# nixie_clock_schematics.net
KiCad netlist of a schematic drawn in EAGLE
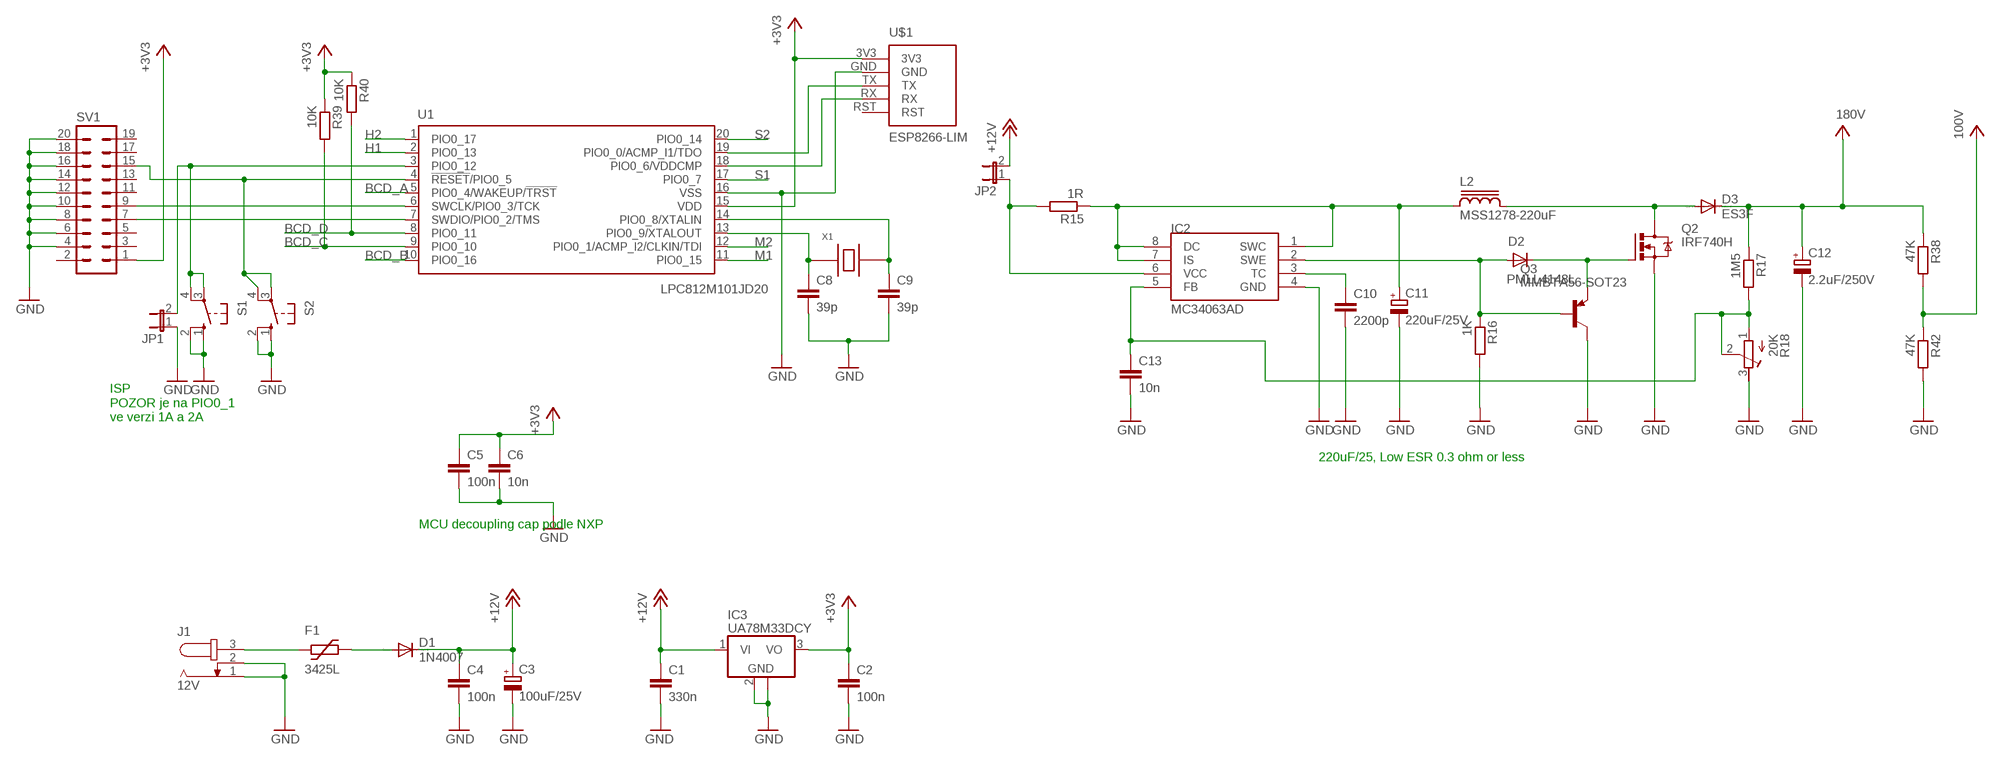
[diagram p0: schematic, sheet 1]
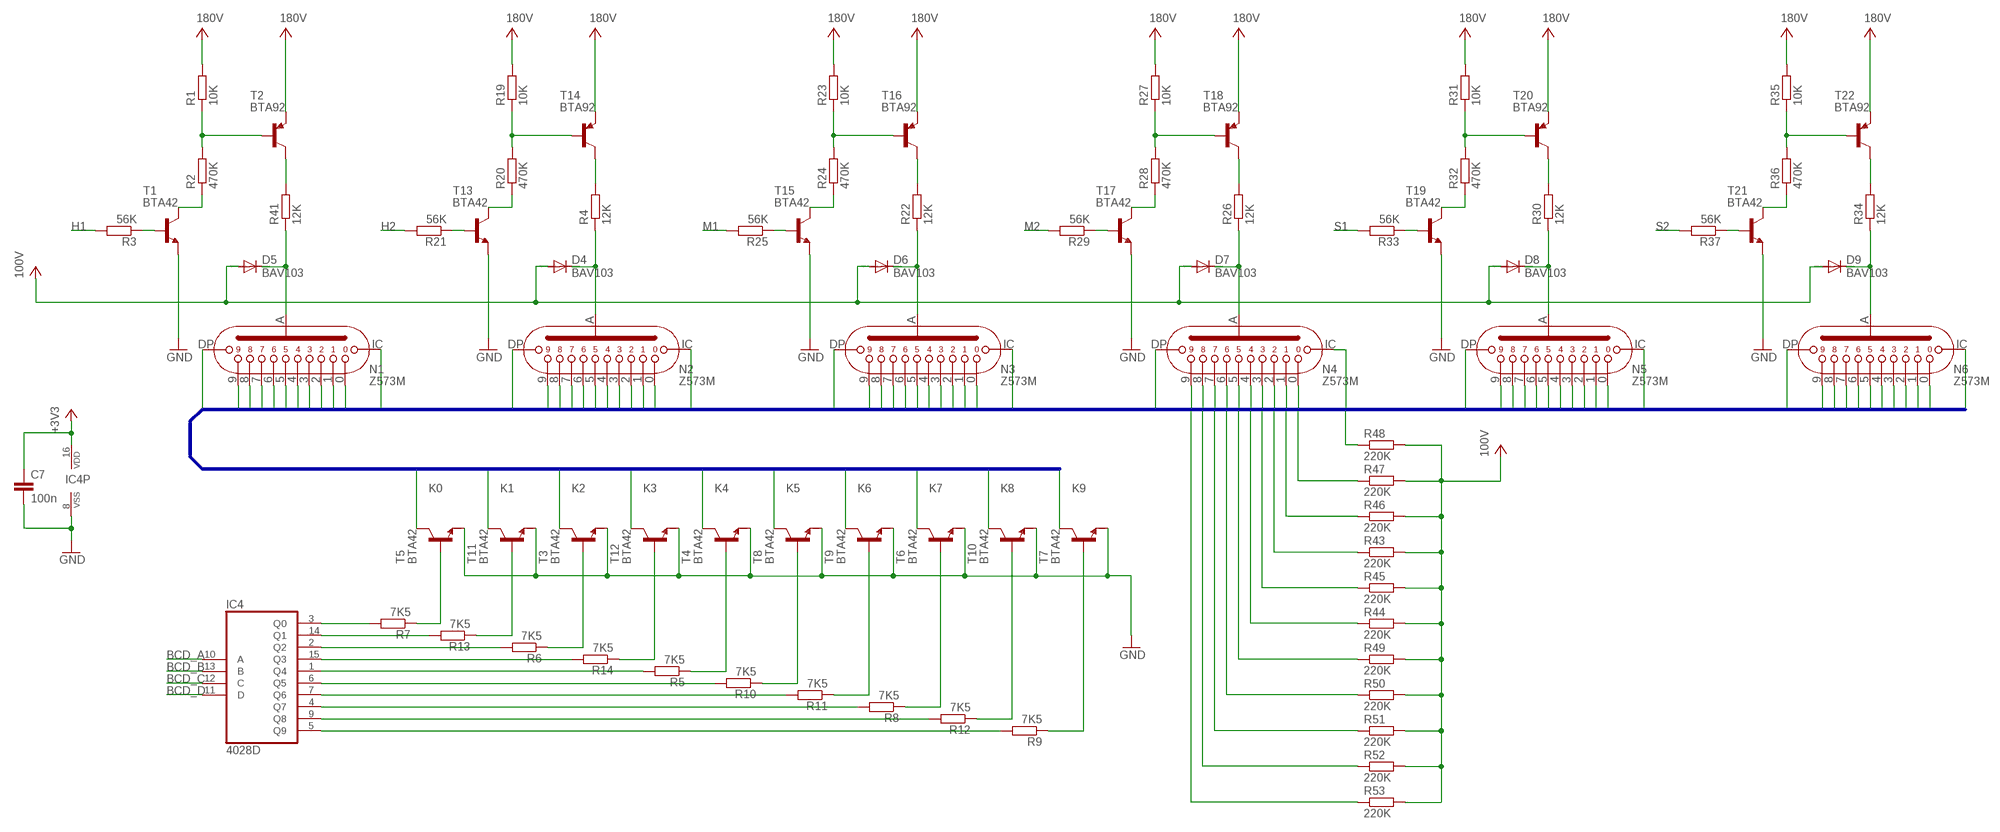
[diagram p1: schematic, sheet 2]

(export (version "E")
  (design (tool "Eeschema 10.0.6"))
  (components
    (comp (ref "C1")
      (value "330n")
      (footprint "eagle-import:C1206")
      (libsource (lib "eagle-import") (part "C-EUC1206"))
    )
    (comp (ref "C2")
      (value "100n")
      (footprint "eagle-import:C1206")
      (libsource (lib "eagle-import") (part "C-EUC1206"))
    )
    (comp (ref "C3")
      (value "100uF/25V")
      (footprint "eagle-import:153CLV-0605")
      (libsource (lib "eagle-import") (part "CPOL-EU153CLV-0605"))
    )
    (comp (ref "C4")
      (value "100n")
      (footprint "eagle-import:C1206")
      (libsource (lib "eagle-import") (part "C-EUC1206"))
    )
    (comp (ref "C5")
      (value "100n")
      (footprint "eagle-import:C1206")
      (libsource (lib "eagle-import") (part "C-EUC1206"))
    )
    (comp (ref "C6")
      (value "10n")
      (footprint "eagle-import:C1206")
      (libsource (lib "eagle-import") (part "C-EUC1206"))
    )
    (comp (ref "C8")
      (value "39p")
      (footprint "eagle-import:C0805")
      (libsource (lib "eagle-import") (part "C-EUC0805"))
    )
    (comp (ref "C9")
      (value "39p")
      (footprint "eagle-import:C0805")
      (libsource (lib "eagle-import") (part "C-EUC0805"))
    )
    (comp (ref "C10")
      (value "2200p")
      (footprint "eagle-import:C1206")
      (libsource (lib "eagle-import") (part "C-EUC1206"))
    )
    (comp (ref "C11")
      (value "220uF/25V")
      (footprint "eagle-import:153CLV-0605")
      (libsource (lib "eagle-import") (part "CPOL-EU153CLV-0605"))
    )
    (comp (ref "C12")
      (value "2.2uF/250V")
      (footprint "eagle-import:E2,5-6")
      (libsource (lib "eagle-import") (part "CPOL-EUE2.5-6"))
    )
    (comp (ref "C13")
      (value "10n")
      (footprint "eagle-import:C1206")
      (libsource (lib "eagle-import") (part "C-EUC1206"))
    )
    (comp (ref "D1")
      (value "1N4007")
      (footprint "eagle-import:MELF-MLL41")
      (libsource (lib "eagle-import") (part "DIODE-MELF-MLL41"))
    )
    (comp (ref "D2")
      (value "PMLL4148L")
      (footprint "eagle-import:SOD80C")
      (libsource (lib "eagle-import") (part "PMLL4148L"))
    )
    (comp (ref "D3")
      (value "ES3F")
      (footprint "eagle-import:SMC")
      (libsource (lib "eagle-import") (part "DIODE-SMC"))
    )
    (comp (ref "F1")
      (value "3425L")
      (footprint "eagle-import:3425L")
      (libsource (lib "eagle-import") (part "3425L"))
    )
    (comp (ref "IC2")
      (value "MC34063AD")
      (footprint "eagle-import:SOIC8")
      (libsource (lib "eagle-import") (part "MC34063AD"))
    )
    (comp (ref "IC3")
      (value "UA78M33DCY")
      (footprint "eagle-import:SOT223")
      (libsource (lib "eagle-import") (part "UA78MDCY33"))
    )
    (comp (ref "J1")
      (value "12V")
      (footprint "eagle-import:SPC4077")
      (libsource (lib "eagle-import") (part "JACK-PLUG0"))
    )
    (comp (ref "JP1")
      (value "JP1E")
      (footprint "eagle-import:JP1")
      (libsource (lib "eagle-import") (part "JP1E"))
    )
    (comp (ref "JP2")
      (value "JP1E")
      (footprint "eagle-import:JP1")
      (libsource (lib "eagle-import") (part "JP1E"))
    )
    (comp (ref "L2")
      (value "MSS1278-220uF")
      (footprint "eagle-import:MSS1278")
      (libsource (lib "eagle-import") (part "MSS1278"))
    )
    (comp (ref "Q2")
      (value "IRF740H")
      (footprint "eagle-import:TO220BH")
      (libsource (lib "eagle-import") (part "IRF740H"))
    )
    (comp (ref "Q3")
      (value "MMBTA56-SOT23")
      (footprint "eagle-import:SOT23")
      (libsource (lib "eagle-import") (part "-?SOT23MMBTA56"))
    )
    (comp (ref "R15")
      (value "1R")
      (footprint "eagle-import:R1206")
      (libsource (lib "eagle-import") (part "R-EU_R1206"))
    )
    (comp (ref "R16")
      (value "1K")
      (footprint "eagle-import:R1206")
      (libsource (lib "eagle-import") (part "R-EU_R1206"))
    )
    (comp (ref "R17")
      (value "1M5")
      (footprint "eagle-import:R1206")
      (libsource (lib "eagle-import") (part "R-EU_R1206"))
    )
    (comp (ref "R18")
      (value "20K")
      (footprint "eagle-import:RTRIM4G_J")
      (libsource (lib "eagle-import") (part "R-TRIMM4G/J"))
    )
    (comp (ref "R38")
      (value "47K")
      (footprint "eagle-import:0207_7")
      (libsource (lib "eagle-import") (part "R-EU_0207/7"))
    )
    (comp (ref "R39")
      (value "10K")
      (footprint "eagle-import:R1206")
      (libsource (lib "eagle-import") (part "R-EU_R1206"))
    )
    (comp (ref "R40")
      (value "10K")
      (footprint "eagle-import:R1206")
      (libsource (lib "eagle-import") (part "R-EU_R1206"))
    )
    (comp (ref "R42")
      (value "47K")
      (footprint "eagle-import:0207_7")
      (libsource (lib "eagle-import") (part "R-EU_0207/7"))
    )
    (comp (ref "S1")
      (value "10-XX")
      (footprint "eagle-import:B3F-10XX")
      (fields (field (name "MPN") "B3F-1000"))
      (libsource (lib "eagle-import") (part "10-XX"))
    )
    (comp (ref "S2")
      (value "10-XX")
      (footprint "eagle-import:B3F-10XX")
      (fields (field (name "MPN") "B3F-1000"))
      (libsource (lib "eagle-import") (part "10-XX"))
    )
    (comp (ref "SV1")
      (value "ML20")
      (footprint "eagle-import:ML20")
      (libsource (lib "eagle-import") (part "ML20"))
    )
    (comp (ref "U$1")
      (value "ESP8266-LIM")
      (footprint "eagle-import:ESP8266-LIM")
      (libsource (lib "eagle-import") (part "ESP8266-LIM"))
    )
    (comp (ref "U1")
      (value "LPC812M101JD20")
      (footprint "eagle-import:SOT163-1")
      (libsource (lib "eagle-import") (part "LPC812M101JD20"))
    )
    (comp (ref "X1")
      (value "SMCE-5032")
      (footprint "eagle-import:IQG5032B")
      (libsource (lib "eagle-import") (part "SMCE-5032"))
    )
    (comp (ref "C7")
      (value "100n")
      (footprint "eagle-import:C1206")
      (libsource (lib "eagle-import") (part "C-EUC1206"))
    )
    (comp (ref "D4")
      (value "BAV103")
      (footprint "eagle-import:MINIMELF")
      (libsource (lib "eagle-import") (part "DIODE-MINIMELF"))
    )
    (comp (ref "D5")
      (value "BAV103")
      (footprint "eagle-import:MINIMELF")
      (libsource (lib "eagle-import") (part "DIODE-MINIMELF"))
    )
    (comp (ref "D6")
      (value "BAV103")
      (footprint "eagle-import:MINIMELF")
      (libsource (lib "eagle-import") (part "DIODE-MINIMELF"))
    )
    (comp (ref "D7")
      (value "BAV103")
      (footprint "eagle-import:MINIMELF")
      (libsource (lib "eagle-import") (part "DIODE-MINIMELF"))
    )
    (comp (ref "D8")
      (value "BAV103")
      (footprint "eagle-import:MINIMELF")
      (libsource (lib "eagle-import") (part "DIODE-MINIMELF"))
    )
    (comp (ref "D9")
      (value "BAV103")
      (footprint "eagle-import:MINIMELF")
      (libsource (lib "eagle-import") (part "DIODE-MINIMELF"))
    )
    (comp (ref "IC4")
      (value "4028D")
      (footprint "eagle-import:SO16")
      (libsource (lib "eagle-import") (part "4028D"))
    )
    (comp (ref "N1")
      (value "Z573M")
      (footprint "eagle-import:Z570M")
      (libsource (lib "eagle-import") (part "Z573M"))
    )
    (comp (ref "N2")
      (value "Z573M")
      (footprint "eagle-import:Z570M")
      (libsource (lib "eagle-import") (part "Z573M"))
    )
    (comp (ref "N3")
      (value "Z573M")
      (footprint "eagle-import:Z570M")
      (libsource (lib "eagle-import") (part "Z573M"))
    )
    (comp (ref "N4")
      (value "Z573M")
      (footprint "eagle-import:Z570M")
      (libsource (lib "eagle-import") (part "Z573M"))
    )
    (comp (ref "N5")
      (value "Z573M")
      (footprint "eagle-import:Z570M")
      (libsource (lib "eagle-import") (part "Z573M"))
    )
    (comp (ref "N6")
      (value "Z573M")
      (footprint "eagle-import:Z570M")
      (libsource (lib "eagle-import") (part "Z573M"))
    )
    (comp (ref "R1")
      (value "10K")
      (footprint "eagle-import:R1206")
      (libsource (lib "eagle-import") (part "R-EU_R1206"))
    )
    (comp (ref "R2")
      (value "470K")
      (footprint "eagle-import:R1206")
      (libsource (lib "eagle-import") (part "R-EU_R1206"))
    )
    (comp (ref "R3")
      (value "56K")
      (footprint "eagle-import:R1206")
      (libsource (lib "eagle-import") (part "R-EU_R1206"))
    )
    (comp (ref "R4")
      (value "12K")
      (footprint "eagle-import:0207_7")
      (libsource (lib "eagle-import") (part "R-EU_0207/7"))
    )
    (comp (ref "R5")
      (value "7K5")
      (footprint "eagle-import:R1206")
      (libsource (lib "eagle-import") (part "R-EU_R1206"))
    )
    (comp (ref "R6")
      (value "7K5")
      (footprint "eagle-import:R1206")
      (libsource (lib "eagle-import") (part "R-EU_R1206"))
    )
    (comp (ref "R7")
      (value "7K5")
      (footprint "eagle-import:R1206")
      (libsource (lib "eagle-import") (part "R-EU_R1206"))
    )
    (comp (ref "R8")
      (value "7K5")
      (footprint "eagle-import:R1206")
      (libsource (lib "eagle-import") (part "R-EU_R1206"))
    )
    (comp (ref "R9")
      (value "7K5")
      (footprint "eagle-import:R1206")
      (libsource (lib "eagle-import") (part "R-EU_R1206"))
    )
    (comp (ref "R10")
      (value "7K5")
      (footprint "eagle-import:R1206")
      (libsource (lib "eagle-import") (part "R-EU_R1206"))
    )
    (comp (ref "R11")
      (value "7K5")
      (footprint "eagle-import:R1206")
      (libsource (lib "eagle-import") (part "R-EU_R1206"))
    )
    (comp (ref "R12")
      (value "7K5")
      (footprint "eagle-import:R1206")
      (libsource (lib "eagle-import") (part "R-EU_R1206"))
    )
    (comp (ref "R13")
      (value "7K5")
      (footprint "eagle-import:R1206")
      (libsource (lib "eagle-import") (part "R-EU_R1206"))
    )
    (comp (ref "R14")
      (value "7K5")
      (footprint "eagle-import:R1206")
      (libsource (lib "eagle-import") (part "R-EU_R1206"))
    )
    (comp (ref "R19")
      (value "10K")
      (footprint "eagle-import:R1206")
      (libsource (lib "eagle-import") (part "R-EU_R1206"))
    )
    (comp (ref "R20")
      (value "470K")
      (footprint "eagle-import:R1206")
      (libsource (lib "eagle-import") (part "R-EU_R1206"))
    )
    (comp (ref "R21")
      (value "56K")
      (footprint "eagle-import:R1206")
      (libsource (lib "eagle-import") (part "R-EU_R1206"))
    )
    (comp (ref "R22")
      (value "12K")
      (footprint "eagle-import:0207_7")
      (libsource (lib "eagle-import") (part "R-EU_0207/7"))
    )
    (comp (ref "R23")
      (value "10K")
      (footprint "eagle-import:R1206")
      (libsource (lib "eagle-import") (part "R-EU_R1206"))
    )
    (comp (ref "R24")
      (value "470K")
      (footprint "eagle-import:R1206")
      (libsource (lib "eagle-import") (part "R-EU_R1206"))
    )
    (comp (ref "R25")
      (value "56K")
      (footprint "eagle-import:R1206")
      (libsource (lib "eagle-import") (part "R-EU_R1206"))
    )
    (comp (ref "R26")
      (value "12K")
      (footprint "eagle-import:0207_7")
      (libsource (lib "eagle-import") (part "R-EU_0207/7"))
    )
    (comp (ref "R27")
      (value "10K")
      (footprint "eagle-import:R1206")
      (libsource (lib "eagle-import") (part "R-EU_R1206"))
    )
    (comp (ref "R28")
      (value "470K")
      (footprint "eagle-import:R1206")
      (libsource (lib "eagle-import") (part "R-EU_R1206"))
    )
    (comp (ref "R29")
      (value "56K")
      (footprint "eagle-import:R1206")
      (libsource (lib "eagle-import") (part "R-EU_R1206"))
    )
    (comp (ref "R30")
      (value "12K")
      (footprint "eagle-import:0207_7")
      (libsource (lib "eagle-import") (part "R-EU_0207/7"))
    )
    (comp (ref "R31")
      (value "10K")
      (footprint "eagle-import:R1206")
      (libsource (lib "eagle-import") (part "R-EU_R1206"))
    )
    (comp (ref "R32")
      (value "470K")
      (footprint "eagle-import:R1206")
      (libsource (lib "eagle-import") (part "R-EU_R1206"))
    )
    (comp (ref "R33")
      (value "56K")
      (footprint "eagle-import:R1206")
      (libsource (lib "eagle-import") (part "R-EU_R1206"))
    )
    (comp (ref "R34")
      (value "12K")
      (footprint "eagle-import:0207_7")
      (libsource (lib "eagle-import") (part "R-EU_0207/7"))
    )
    (comp (ref "R35")
      (value "10K")
      (footprint "eagle-import:R1206")
      (libsource (lib "eagle-import") (part "R-EU_R1206"))
    )
    (comp (ref "R36")
      (value "470K")
      (footprint "eagle-import:R1206")
      (libsource (lib "eagle-import") (part "R-EU_R1206"))
    )
    (comp (ref "R37")
      (value "56K")
      (footprint "eagle-import:R1206")
      (libsource (lib "eagle-import") (part "R-EU_R1206"))
    )
    (comp (ref "R41")
      (value "12K")
      (footprint "eagle-import:0207_7")
      (libsource (lib "eagle-import") (part "R-EU_0207/7"))
    )
    (comp (ref "R43")
      (value "220K")
      (footprint "eagle-import:R1206")
      (libsource (lib "eagle-import") (part "R-EU_R1206"))
    )
    (comp (ref "R44")
      (value "220K")
      (footprint "eagle-import:R1206")
      (libsource (lib "eagle-import") (part "R-EU_R1206"))
    )
    (comp (ref "R45")
      (value "220K")
      (footprint "eagle-import:R1206")
      (libsource (lib "eagle-import") (part "R-EU_R1206"))
    )
    (comp (ref "R46")
      (value "220K")
      (footprint "eagle-import:R1206")
      (libsource (lib "eagle-import") (part "R-EU_R1206"))
    )
    (comp (ref "R47")
      (value "220K")
      (footprint "eagle-import:R1206")
      (libsource (lib "eagle-import") (part "R-EU_R1206"))
    )
    (comp (ref "R48")
      (value "220K")
      (footprint "eagle-import:R1206")
      (libsource (lib "eagle-import") (part "R-EU_R1206"))
    )
    (comp (ref "R49")
      (value "220K")
      (footprint "eagle-import:R1206")
      (libsource (lib "eagle-import") (part "R-EU_R1206"))
    )
    (comp (ref "R50")
      (value "220K")
      (footprint "eagle-import:R1206")
      (libsource (lib "eagle-import") (part "R-EU_R1206"))
    )
    (comp (ref "R51")
      (value "220K")
      (footprint "eagle-import:R1206")
      (libsource (lib "eagle-import") (part "R-EU_R1206"))
    )
    (comp (ref "R52")
      (value "220K")
      (footprint "eagle-import:R1206")
      (libsource (lib "eagle-import") (part "R-EU_R1206"))
    )
    (comp (ref "R53")
      (value "220K")
      (footprint "eagle-import:R1206")
      (libsource (lib "eagle-import") (part "R-EU_R1206"))
    )
    (comp (ref "T1")
      (value "BTA42")
      (footprint "eagle-import:SOT23-BEC")
      (libsource (lib "eagle-import") (part "-NPN-SOT23-BECMMBTA42LT1"))
    )
    (comp (ref "T2")
      (value "BTA92")
      (footprint "eagle-import:SOT23-BEC")
      (libsource (lib "eagle-import") (part "-PNP-SOT23-BECMMBTA92LT1"))
    )
    (comp (ref "T3")
      (value "BTA42")
      (footprint "eagle-import:SOT23-BEC")
      (libsource (lib "eagle-import") (part "-NPN-SOT23-BECMMBTA42LT1"))
    )
    (comp (ref "T4")
      (value "BTA42")
      (footprint "eagle-import:SOT23-BEC")
      (libsource (lib "eagle-import") (part "-NPN-SOT23-BECMMBTA42LT1"))
    )
    (comp (ref "T5")
      (value "BTA42")
      (footprint "eagle-import:SOT23-BEC")
      (libsource (lib "eagle-import") (part "-NPN-SOT23-BECMMBTA42LT1"))
    )
    (comp (ref "T6")
      (value "BTA42")
      (footprint "eagle-import:SOT23-BEC")
      (libsource (lib "eagle-import") (part "-NPN-SOT23-BECMMBTA42LT1"))
    )
    (comp (ref "T7")
      (value "BTA42")
      (footprint "eagle-import:SOT23-BEC")
      (libsource (lib "eagle-import") (part "-NPN-SOT23-BECMMBTA42LT1"))
    )
    (comp (ref "T8")
      (value "BTA42")
      (footprint "eagle-import:SOT23-BEC")
      (libsource (lib "eagle-import") (part "-NPN-SOT23-BECMMBTA42LT1"))
    )
    (comp (ref "T9")
      (value "BTA42")
      (footprint "eagle-import:SOT23-BEC")
      (libsource (lib "eagle-import") (part "-NPN-SOT23-BECMMBTA42LT1"))
    )
    (comp (ref "T10")
      (value "BTA42")
      (footprint "eagle-import:SOT23-BEC")
      (libsource (lib "eagle-import") (part "-NPN-SOT23-BECMMBTA42LT1"))
    )
    (comp (ref "T11")
      (value "BTA42")
      (footprint "eagle-import:SOT23-BEC")
      (libsource (lib "eagle-import") (part "-NPN-SOT23-BECMMBTA42LT1"))
    )
    (comp (ref "T12")
      (value "BTA42")
      (footprint "eagle-import:SOT23-BEC")
      (libsource (lib "eagle-import") (part "-NPN-SOT23-BECMMBTA42LT1"))
    )
    (comp (ref "T13")
      (value "BTA42")
      (footprint "eagle-import:SOT23-BEC")
      (libsource (lib "eagle-import") (part "-NPN-SOT23-BECMMBTA42LT1"))
    )
    (comp (ref "T14")
      (value "BTA92")
      (footprint "eagle-import:SOT23-BEC")
      (libsource (lib "eagle-import") (part "-PNP-SOT23-BECMMBTA92LT1"))
    )
    (comp (ref "T15")
      (value "BTA42")
      (footprint "eagle-import:SOT23-BEC")
      (libsource (lib "eagle-import") (part "-NPN-SOT23-BECMMBTA42LT1"))
    )
    (comp (ref "T16")
      (value "BTA92")
      (footprint "eagle-import:SOT23-BEC")
      (libsource (lib "eagle-import") (part "-PNP-SOT23-BECMMBTA92LT1"))
    )
    (comp (ref "T17")
      (value "BTA42")
      (footprint "eagle-import:SOT23-BEC")
      (libsource (lib "eagle-import") (part "-NPN-SOT23-BECMMBTA42LT1"))
    )
    (comp (ref "T18")
      (value "BTA92")
      (footprint "eagle-import:SOT23-BEC")
      (libsource (lib "eagle-import") (part "-PNP-SOT23-BECMMBTA92LT1"))
    )
    (comp (ref "T19")
      (value "BTA42")
      (footprint "eagle-import:SOT23-BEC")
      (libsource (lib "eagle-import") (part "-NPN-SOT23-BECMMBTA42LT1"))
    )
    (comp (ref "T20")
      (value "BTA92")
      (footprint "eagle-import:SOT23-BEC")
      (libsource (lib "eagle-import") (part "-PNP-SOT23-BECMMBTA92LT1"))
    )
    (comp (ref "T21")
      (value "BTA42")
      (footprint "eagle-import:SOT23-BEC")
      (libsource (lib "eagle-import") (part "-NPN-SOT23-BECMMBTA42LT1"))
    )
    (comp (ref "T22")
      (value "BTA92")
      (footprint "eagle-import:SOT23-BEC")
      (libsource (lib "eagle-import") (part "-PNP-SOT23-BECMMBTA92LT1"))
    )
  )
  (nets
    (net (code "1") (name "+3V3") (class "Default")
      (node (ref "C2") (pin "1") (pinfunction "1_1") (pintype "passive"))
      (node (ref "C5") (pin "1") (pinfunction "1_1") (pintype "passive"))
      (node (ref "C6") (pin "1") (pinfunction "1_1") (pintype "passive"))
      (node (ref "C7") (pin "1") (pinfunction "1_1") (pintype "passive"))
      (node (ref "IC3") (pin "3") (pinfunction "VO_3") (pintype "passive"))
      (node (ref "IC4") (pin "16") (pinfunction "VDD_16") (pintype "power_in"))
      (node (ref "R39") (pin "1") (pinfunction "1_1") (pintype "passive"))
      (node (ref "R40") (pin "1") (pinfunction "1_1") (pintype "passive"))
      (node (ref "SV1") (pin "1") (pinfunction "1_1") (pintype "passive"))
      (node (ref "U$1") (pin "3V3") (pinfunction "3V3_3V3") (pintype "power_in"))
      (node (ref "U1") (pin "15") (pinfunction "VDD_15") (pintype "power_in"))
    )
    (net (code "2") (name "+12V") (class "Default")
      (node (ref "C1") (pin "1") (pinfunction "1_1") (pintype "passive"))
      (node (ref "C3") (pin "+") (pinfunction "+_+") (pintype "passive"))
      (node (ref "C4") (pin "1") (pinfunction "1_1") (pintype "passive"))
      (node (ref "D1") (pin "C") (pinfunction "C_C") (pintype "passive"))
      (node (ref "IC3") (pin "1") (pinfunction "VI_1") (pintype "input"))
      (node (ref "JP2") (pin "2") (pinfunction "2_2") (pintype "passive"))
    )
    (net (code "3") (name "100V") (class "Default")
      (node (ref "D4") (pin "A") (pinfunction "A_A") (pintype "passive"))
      (node (ref "D5") (pin "A") (pinfunction "A_A") (pintype "passive"))
      (node (ref "D6") (pin "A") (pinfunction "A_A") (pintype "passive"))
      (node (ref "D7") (pin "A") (pinfunction "A_A") (pintype "passive"))
      (node (ref "D8") (pin "A") (pinfunction "A_A") (pintype "passive"))
      (node (ref "D9") (pin "A") (pinfunction "A_A") (pintype "passive"))
      (node (ref "R38") (pin "2") (pinfunction "2_2") (pintype "passive"))
      (node (ref "R42") (pin "1") (pinfunction "1_1") (pintype "passive"))
      (node (ref "R43") (pin "2") (pinfunction "2_2") (pintype "passive"))
      (node (ref "R44") (pin "2") (pinfunction "2_2") (pintype "passive"))
      (node (ref "R45") (pin "2") (pinfunction "2_2") (pintype "passive"))
      (node (ref "R46") (pin "2") (pinfunction "2_2") (pintype "passive"))
      (node (ref "R47") (pin "2") (pinfunction "2_2") (pintype "passive"))
      (node (ref "R48") (pin "2") (pinfunction "2_2") (pintype "passive"))
      (node (ref "R49") (pin "2") (pinfunction "2_2") (pintype "passive"))
      (node (ref "R50") (pin "2") (pinfunction "2_2") (pintype "passive"))
      (node (ref "R51") (pin "2") (pinfunction "2_2") (pintype "passive"))
      (node (ref "R52") (pin "2") (pinfunction "2_2") (pintype "passive"))
      (node (ref "R53") (pin "2") (pinfunction "2_2") (pintype "passive"))
    )
    (net (code "4") (name "180V") (class "Default")
      (node (ref "C12") (pin "+") (pinfunction "+_+") (pintype "passive"))
      (node (ref "D3") (pin "C") (pinfunction "C_C") (pintype "passive"))
      (node (ref "R1") (pin "2") (pinfunction "2_2") (pintype "passive"))
      (node (ref "R17") (pin "1") (pinfunction "1_1") (pintype "passive"))
      (node (ref "R19") (pin "2") (pinfunction "2_2") (pintype "passive"))
      (node (ref "R23") (pin "2") (pinfunction "2_2") (pintype "passive"))
      (node (ref "R27") (pin "2") (pinfunction "2_2") (pintype "passive"))
      (node (ref "R31") (pin "2") (pinfunction "2_2") (pintype "passive"))
      (node (ref "R35") (pin "2") (pinfunction "2_2") (pintype "passive"))
      (node (ref "R38") (pin "1") (pinfunction "1_1") (pintype "passive"))
      (node (ref "T14") (pin "E") (pinfunction "E_E") (pintype "passive"))
      (node (ref "T16") (pin "E") (pinfunction "E_E") (pintype "passive"))
      (node (ref "T18") (pin "E") (pinfunction "E_E") (pintype "passive"))
      (node (ref "T2") (pin "E") (pinfunction "E_E") (pintype "passive"))
      (node (ref "T20") (pin "E") (pinfunction "E_E") (pintype "passive"))
      (node (ref "T22") (pin "E") (pinfunction "E_E") (pintype "passive"))
    )
    (net (code "5") (name "BCD_A") (class "Default")
      (node (ref "IC4") (pin "10") (pinfunction "A_10") (pintype "input"))
      (node (ref "U1") (pin "5") (pinfunction "PIO0_4/WAKEUP/~{TRST}_5") (pintype "bidirectional"))
    )
    (net (code "6") (name "BCD_B") (class "Default")
      (node (ref "IC4") (pin "13") (pinfunction "B_13") (pintype "input"))
      (node (ref "U1") (pin "10") (pinfunction "PIO0_16_10") (pintype "bidirectional"))
    )
    (net (code "7") (name "BCD_C") (class "Default")
      (node (ref "IC4") (pin "12") (pinfunction "C_12") (pintype "input"))
      (node (ref "R39") (pin "2") (pinfunction "2_2") (pintype "passive"))
      (node (ref "U1") (pin "9") (pinfunction "PIO0_10_9") (pintype "bidirectional"))
    )
    (net (code "8") (name "BCD_D") (class "Default")
      (node (ref "IC4") (pin "11") (pinfunction "D_11") (pintype "input"))
      (node (ref "R40") (pin "2") (pinfunction "2_2") (pintype "passive"))
      (node (ref "U1") (pin "8") (pinfunction "PIO0_11_8") (pintype "bidirectional"))
    )
    (net (code "9") (name "GND") (class "Default")
      (node (ref "C1") (pin "2") (pinfunction "2_2") (pintype "passive"))
      (node (ref "C10") (pin "2") (pinfunction "2_2") (pintype "passive"))
      (node (ref "C11") (pin "-") (pinfunction "-_-") (pintype "passive"))
      (node (ref "C12") (pin "-") (pinfunction "-_-") (pintype "passive"))
      (node (ref "C13") (pin "2") (pinfunction "2_2") (pintype "passive"))
      (node (ref "C2") (pin "2") (pinfunction "2_2") (pintype "passive"))
      (node (ref "C3") (pin "-") (pinfunction "-_-") (pintype "passive"))
      (node (ref "C4") (pin "2") (pinfunction "2_2") (pintype "passive"))
      (node (ref "C5") (pin "2") (pinfunction "2_2") (pintype "passive"))
      (node (ref "C6") (pin "2") (pinfunction "2_2") (pintype "passive"))
      (node (ref "C7") (pin "2") (pinfunction "2_2") (pintype "passive"))
      (node (ref "C8") (pin "2") (pinfunction "2_2") (pintype "passive"))
      (node (ref "C9") (pin "2") (pinfunction "2_2") (pintype "passive"))
      (node (ref "IC2") (pin "4") (pinfunction "GND_4") (pintype "passive"))
      (node (ref "IC3") (pin "2") (pinfunction "GND_2") (pintype "passive"))
      (node (ref "IC3") (pin "4") (pinfunction "GND_4") (pintype "passive"))
      (node (ref "IC4") (pin "8") (pinfunction "VSS_8") (pintype "power_in"))
      (node (ref "J1") (pin "1") (pinfunction "1_1") (pintype "passive"))
      (node (ref "J1") (pin "2") (pinfunction "2_2") (pintype "passive"))
      (node (ref "JP1") (pin "1") (pinfunction "1_1") (pintype "passive"))
      (node (ref "Q2") (pin "S") (pinfunction "S_S") (pintype "passive"))
      (node (ref "Q3") (pin "3") (pinfunction "C_3") (pintype "passive"))
      (node (ref "R16") (pin "2") (pinfunction "2_2") (pintype "passive"))
      (node (ref "R18") (pin "3") (pinfunction "E_3") (pintype "passive"))
      (node (ref "R42") (pin "2") (pinfunction "2_2") (pintype "passive"))
      (node (ref "S1") (pin "1") (pinfunction "S_1") (pintype "passive"))
      (node (ref "S1") (pin "2") (pinfunction "S1_2") (pintype "passive"))
      (node (ref "S2") (pin "1") (pinfunction "S_1") (pintype "passive"))
      (node (ref "S2") (pin "2") (pinfunction "S1_2") (pintype "passive"))
      (node (ref "SV1") (pin "10") (pinfunction "10_10") (pintype "passive"))
      (node (ref "SV1") (pin "12") (pinfunction "12_12") (pintype "passive"))
      (node (ref "SV1") (pin "14") (pinfunction "14_14") (pintype "passive"))
      (node (ref "SV1") (pin "16") (pinfunction "16_16") (pintype "passive"))
      (node (ref "SV1") (pin "18") (pinfunction "18_18") (pintype "passive"))
      (node (ref "SV1") (pin "20") (pinfunction "20_20") (pintype "passive"))
      (node (ref "SV1") (pin "4") (pinfunction "4_4") (pintype "passive"))
      (node (ref "SV1") (pin "6") (pinfunction "6_6") (pintype "passive"))
      (node (ref "SV1") (pin "8") (pinfunction "8_8") (pintype "passive"))
      (node (ref "T1") (pin "E") (pinfunction "E_E") (pintype "passive"))
      (node (ref "T10") (pin "E") (pinfunction "E_E") (pintype "passive"))
      (node (ref "T11") (pin "E") (pinfunction "E_E") (pintype "passive"))
      (node (ref "T12") (pin "E") (pinfunction "E_E") (pintype "passive"))
      (node (ref "T13") (pin "E") (pinfunction "E_E") (pintype "passive"))
      (node (ref "T15") (pin "E") (pinfunction "E_E") (pintype "passive"))
      (node (ref "T17") (pin "E") (pinfunction "E_E") (pintype "passive"))
      (node (ref "T19") (pin "E") (pinfunction "E_E") (pintype "passive"))
      (node (ref "T21") (pin "E") (pinfunction "E_E") (pintype "passive"))
      (node (ref "T3") (pin "E") (pinfunction "E_E") (pintype "passive"))
      (node (ref "T4") (pin "E") (pinfunction "E_E") (pintype "passive"))
      (node (ref "T5") (pin "E") (pinfunction "E_E") (pintype "passive"))
      (node (ref "T6") (pin "E") (pinfunction "E_E") (pintype "passive"))
      (node (ref "T7") (pin "E") (pinfunction "E_E") (pintype "passive"))
      (node (ref "T8") (pin "E") (pinfunction "E_E") (pintype "passive"))
      (node (ref "T9") (pin "E") (pinfunction "E_E") (pintype "passive"))
      (node (ref "U$1") (pin "GND") (pinfunction "GND_GND") (pintype "power_in"))
      (node (ref "U1") (pin "16") (pinfunction "VSS_16") (pintype "power_in"))
    )
    (net (code "10") (name "H1") (class "Default")
      (node (ref "R3") (pin "2") (pinfunction "2_2") (pintype "passive"))
      (node (ref "U1") (pin "2") (pinfunction "PIO0_13_2") (pintype "bidirectional"))
    )
    (net (code "11") (name "H2") (class "Default")
      (node (ref "R21") (pin "2") (pinfunction "2_2") (pintype "passive"))
      (node (ref "U1") (pin "1") (pinfunction "PIO0_17_1") (pintype "bidirectional"))
    )
    (net (code "12") (name "K0") (class "Default")
      (node (ref "N1") (pin "12") (pinfunction "0_12") (pintype "bidirectional"))
      (node (ref "N2") (pin "12") (pinfunction "0_12") (pintype "bidirectional"))
      (node (ref "N3") (pin "12") (pinfunction "0_12") (pintype "bidirectional"))
      (node (ref "N4") (pin "12") (pinfunction "0_12") (pintype "bidirectional"))
      (node (ref "N5") (pin "12") (pinfunction "0_12") (pintype "bidirectional"))
      (node (ref "N6") (pin "12") (pinfunction "0_12") (pintype "bidirectional"))
      (node (ref "R47") (pin "1") (pinfunction "1_1") (pintype "passive"))
      (node (ref "T5") (pin "C") (pinfunction "C_C") (pintype "passive"))
    )
    (net (code "13") (name "K1") (class "Default")
      (node (ref "N1") (pin "1") (pinfunction "1_1") (pintype "bidirectional"))
      (node (ref "N2") (pin "1") (pinfunction "1_1") (pintype "bidirectional"))
      (node (ref "N3") (pin "1") (pinfunction "1_1") (pintype "bidirectional"))
      (node (ref "N4") (pin "1") (pinfunction "1_1") (pintype "bidirectional"))
      (node (ref "N5") (pin "1") (pinfunction "1_1") (pintype "bidirectional"))
      (node (ref "N6") (pin "1") (pinfunction "1_1") (pintype "bidirectional"))
      (node (ref "R46") (pin "1") (pinfunction "1_1") (pintype "passive"))
      (node (ref "T11") (pin "C") (pinfunction "C_C") (pintype "passive"))
    )
    (net (code "14") (name "K2") (class "Default")
      (node (ref "N1") (pin "2") (pinfunction "2_2") (pintype "bidirectional"))
      (node (ref "N2") (pin "2") (pinfunction "2_2") (pintype "bidirectional"))
      (node (ref "N3") (pin "2") (pinfunction "2_2") (pintype "bidirectional"))
      (node (ref "N4") (pin "2") (pinfunction "2_2") (pintype "bidirectional"))
      (node (ref "N5") (pin "2") (pinfunction "2_2") (pintype "bidirectional"))
      (node (ref "N6") (pin "2") (pinfunction "2_2") (pintype "bidirectional"))
      (node (ref "R43") (pin "1") (pinfunction "1_1") (pintype "passive"))
      (node (ref "T3") (pin "C") (pinfunction "C_C") (pintype "passive"))
    )
    (net (code "15") (name "K3") (class "Default")
      (node (ref "N1") (pin "3") (pinfunction "3_3") (pintype "bidirectional"))
      (node (ref "N2") (pin "3") (pinfunction "3_3") (pintype "bidirectional"))
      (node (ref "N3") (pin "3") (pinfunction "3_3") (pintype "bidirectional"))
      (node (ref "N4") (pin "3") (pinfunction "3_3") (pintype "bidirectional"))
      (node (ref "N5") (pin "3") (pinfunction "3_3") (pintype "bidirectional"))
      (node (ref "N6") (pin "3") (pinfunction "3_3") (pintype "bidirectional"))
      (node (ref "R45") (pin "1") (pinfunction "1_1") (pintype "passive"))
      (node (ref "T12") (pin "C") (pinfunction "C_C") (pintype "passive"))
    )
    (net (code "16") (name "K4") (class "Default")
      (node (ref "N1") (pin "5") (pinfunction "4_5") (pintype "bidirectional"))
      (node (ref "N2") (pin "5") (pinfunction "4_5") (pintype "bidirectional"))
      (node (ref "N3") (pin "5") (pinfunction "4_5") (pintype "bidirectional"))
      (node (ref "N4") (pin "5") (pinfunction "4_5") (pintype "bidirectional"))
      (node (ref "N5") (pin "5") (pinfunction "4_5") (pintype "bidirectional"))
      (node (ref "N6") (pin "5") (pinfunction "4_5") (pintype "bidirectional"))
      (node (ref "R44") (pin "1") (pinfunction "1_1") (pintype "passive"))
      (node (ref "T4") (pin "C") (pinfunction "C_C") (pintype "passive"))
    )
    (net (code "17") (name "K5") (class "Default")
      (node (ref "N1") (pin "6") (pinfunction "5_6") (pintype "bidirectional"))
      (node (ref "N2") (pin "6") (pinfunction "5_6") (pintype "bidirectional"))
      (node (ref "N3") (pin "6") (pinfunction "5_6") (pintype "bidirectional"))
      (node (ref "N4") (pin "6") (pinfunction "5_6") (pintype "bidirectional"))
      (node (ref "N5") (pin "6") (pinfunction "5_6") (pintype "bidirectional"))
      (node (ref "N6") (pin "6") (pinfunction "5_6") (pintype "bidirectional"))
      (node (ref "R49") (pin "1") (pinfunction "1_1") (pintype "passive"))
      (node (ref "T8") (pin "C") (pinfunction "C_C") (pintype "passive"))
    )
    (net (code "18") (name "K6") (class "Default")
      (node (ref "N1") (pin "7") (pinfunction "6_7") (pintype "bidirectional"))
      (node (ref "N2") (pin "7") (pinfunction "6_7") (pintype "bidirectional"))
      (node (ref "N3") (pin "7") (pinfunction "6_7") (pintype "bidirectional"))
      (node (ref "N4") (pin "7") (pinfunction "6_7") (pintype "bidirectional"))
      (node (ref "N5") (pin "7") (pinfunction "6_7") (pintype "bidirectional"))
      (node (ref "N6") (pin "7") (pinfunction "6_7") (pintype "bidirectional"))
      (node (ref "R50") (pin "1") (pinfunction "1_1") (pintype "passive"))
      (node (ref "T9") (pin "C") (pinfunction "C_C") (pintype "passive"))
    )
    (net (code "19") (name "K7") (class "Default")
      (node (ref "N1") (pin "8") (pinfunction "7_8") (pintype "bidirectional"))
      (node (ref "N2") (pin "8") (pinfunction "7_8") (pintype "bidirectional"))
      (node (ref "N3") (pin "8") (pinfunction "7_8") (pintype "bidirectional"))
      (node (ref "N4") (pin "8") (pinfunction "7_8") (pintype "bidirectional"))
      (node (ref "N5") (pin "8") (pinfunction "7_8") (pintype "bidirectional"))
      (node (ref "N6") (pin "8") (pinfunction "7_8") (pintype "bidirectional"))
      (node (ref "R51") (pin "1") (pinfunction "1_1") (pintype "passive"))
      (node (ref "T6") (pin "C") (pinfunction "C_C") (pintype "passive"))
    )
    (net (code "20") (name "K8") (class "Default")
      (node (ref "N1") (pin "9") (pinfunction "8_9") (pintype "bidirectional"))
      (node (ref "N2") (pin "9") (pinfunction "8_9") (pintype "bidirectional"))
      (node (ref "N3") (pin "9") (pinfunction "8_9") (pintype "bidirectional"))
      (node (ref "N4") (pin "9") (pinfunction "8_9") (pintype "bidirectional"))
      (node (ref "N5") (pin "9") (pinfunction "8_9") (pintype "bidirectional"))
      (node (ref "N6") (pin "9") (pinfunction "8_9") (pintype "bidirectional"))
      (node (ref "R52") (pin "1") (pinfunction "1_1") (pintype "passive"))
      (node (ref "T10") (pin "C") (pinfunction "C_C") (pintype "passive"))
    )
    (net (code "21") (name "K9") (class "Default")
      (node (ref "N1") (pin "11") (pinfunction "9_11") (pintype "bidirectional"))
      (node (ref "N2") (pin "11") (pinfunction "9_11") (pintype "bidirectional"))
      (node (ref "N3") (pin "11") (pinfunction "9_11") (pintype "bidirectional"))
      (node (ref "N4") (pin "11") (pinfunction "9_11") (pintype "bidirectional"))
      (node (ref "N5") (pin "11") (pinfunction "9_11") (pintype "bidirectional"))
      (node (ref "N6") (pin "11") (pinfunction "9_11") (pintype "bidirectional"))
      (node (ref "R53") (pin "1") (pinfunction "1_1") (pintype "passive"))
      (node (ref "T7") (pin "C") (pinfunction "C_C") (pintype "passive"))
    )
    (net (code "22") (name "K10") (class "Default")
      (node (ref "N1") (pin "10") (pinfunction "DP_10") (pintype "bidirectional"))
      (node (ref "N1") (pin "4") (pinfunction "IC_4") (pintype "bidirectional"))
      (node (ref "N2") (pin "10") (pinfunction "DP_10") (pintype "bidirectional"))
      (node (ref "N2") (pin "4") (pinfunction "IC_4") (pintype "bidirectional"))
      (node (ref "N3") (pin "10") (pinfunction "DP_10") (pintype "bidirectional"))
      (node (ref "N3") (pin "4") (pinfunction "IC_4") (pintype "bidirectional"))
      (node (ref "N4") (pin "10") (pinfunction "DP_10") (pintype "bidirectional"))
      (node (ref "N4") (pin "4") (pinfunction "IC_4") (pintype "bidirectional"))
      (node (ref "N5") (pin "10") (pinfunction "DP_10") (pintype "bidirectional"))
      (node (ref "N5") (pin "4") (pinfunction "IC_4") (pintype "bidirectional"))
      (node (ref "N6") (pin "10") (pinfunction "DP_10") (pintype "bidirectional"))
      (node (ref "N6") (pin "4") (pinfunction "IC_4") (pintype "bidirectional"))
      (node (ref "R48") (pin "1") (pinfunction "1_1") (pintype "passive"))
    )
    (net (code "23") (name "M1") (class "Default")
      (node (ref "R25") (pin "2") (pinfunction "2_2") (pintype "passive"))
      (node (ref "U1") (pin "11") (pinfunction "PIO0_15_11") (pintype "bidirectional"))
    )
    (net (code "24") (name "M2") (class "Default")
      (node (ref "R29") (pin "2") (pinfunction "2_2") (pintype "passive"))
      (node (ref "U1") (pin "12") (pinfunction "PIO0_1/ACMP_I2/CLKIN/TDI_12") (pintype "bidirectional"))
    )
    (net (code "25") (name "Net-(D2-A)") (class "Default")
      (node (ref "D2") (pin "2") (pinfunction "A_2") (pintype "passive"))
      (node (ref "IC2") (pin "2") (pinfunction "SWE_2") (pintype "passive"))
      (node (ref "Q3") (pin "1") (pinfunction "B_1") (pintype "passive"))
      (node (ref "R16") (pin "1") (pinfunction "1_1") (pintype "passive"))
    )
    (net (code "26") (name "Net-(D2-K)") (class "Default")
      (node (ref "D2") (pin "1") (pinfunction "K_1") (pintype "passive"))
      (node (ref "Q2") (pin "G") (pinfunction "G_G") (pintype "passive"))
      (node (ref "Q3") (pin "2") (pinfunction "E_2") (pintype "passive"))
    )
    (net (code "27") (name "Net-(D3-PadA)") (class "Default")
      (node (ref "D3") (pin "A") (pinfunction "A_A") (pintype "passive"))
      (node (ref "L2") (pin "2") (pinfunction "2_2") (pintype "passive"))
      (node (ref "Q2") (pin "D") (pinfunction "D_D") (pintype "passive"))
    )
    (net (code "28") (name "Net-(F1-1)") (class "Default")
      (node (ref "F1") (pin "P$1") (pinfunction "1_P$1") (pintype "passive"))
      (node (ref "J1") (pin "3") (pinfunction "3_3") (pintype "passive"))
    )
    (net (code "29") (name "Net-(F1-2)") (class "Default")
      (node (ref "D1") (pin "A") (pinfunction "A_A") (pintype "passive"))
      (node (ref "F1") (pin "P$2") (pinfunction "2_P$2") (pintype "passive"))
    )
    (net (code "30") (name "Net-(IC2-DC)") (class "Default")
      (node (ref "C11") (pin "+") (pinfunction "+_+") (pintype "passive"))
      (node (ref "IC2") (pin "1") (pinfunction "SWC_1") (pintype "passive"))
      (node (ref "IC2") (pin "7") (pinfunction "IS_7") (pintype "passive"))
      (node (ref "IC2") (pin "8") (pinfunction "DC_8") (pintype "passive"))
      (node (ref "L2") (pin "1") (pinfunction "1_1") (pintype "passive"))
      (node (ref "R15") (pin "1") (pinfunction "1_1") (pintype "passive"))
    )
    (net (code "31") (name "Net-(IC2-FB)") (class "Default")
      (node (ref "C13") (pin "1") (pinfunction "1_1") (pintype "passive"))
      (node (ref "IC2") (pin "5") (pinfunction "FB_5") (pintype "passive"))
      (node (ref "R17") (pin "2") (pinfunction "2_2") (pintype "passive"))
      (node (ref "R18") (pin "1") (pinfunction "A_1") (pintype "passive"))
      (node (ref "R18") (pin "2") (pinfunction "S_2") (pintype "passive"))
    )
    (net (code "32") (name "Net-(IC2-TC)") (class "Default")
      (node (ref "C10") (pin "1") (pinfunction "1_1") (pintype "passive"))
      (node (ref "IC2") (pin "3") (pinfunction "TC_3") (pintype "passive"))
    )
    (net (code "33") (name "Net-(IC2-VCC)") (class "Default")
      (node (ref "IC2") (pin "6") (pinfunction "VCC_6") (pintype "passive"))
      (node (ref "JP2") (pin "1") (pinfunction "1_1") (pintype "passive"))
      (node (ref "R15") (pin "2") (pinfunction "2_2") (pintype "passive"))
    )
    (net (code "34") (name "Net-(IC4A-Q0)") (class "Default")
      (node (ref "IC4") (pin "3") (pinfunction "Q0_3") (pintype "output"))
      (node (ref "R7") (pin "2") (pinfunction "2_2") (pintype "passive"))
    )
    (net (code "35") (name "Net-(IC4A-Q1)") (class "Default")
      (node (ref "IC4") (pin "14") (pinfunction "Q1_14") (pintype "output"))
      (node (ref "R13") (pin "2") (pinfunction "2_2") (pintype "passive"))
    )
    (net (code "36") (name "Net-(IC4A-Q2)") (class "Default")
      (node (ref "IC4") (pin "2") (pinfunction "Q2_2") (pintype "output"))
      (node (ref "R6") (pin "2") (pinfunction "2_2") (pintype "passive"))
    )
    (net (code "37") (name "Net-(IC4A-Q3)") (class "Default")
      (node (ref "IC4") (pin "15") (pinfunction "Q3_15") (pintype "output"))
      (node (ref "R14") (pin "2") (pinfunction "2_2") (pintype "passive"))
    )
    (net (code "38") (name "Net-(IC4A-Q4)") (class "Default")
      (node (ref "IC4") (pin "1") (pinfunction "Q4_1") (pintype "output"))
      (node (ref "R5") (pin "2") (pinfunction "2_2") (pintype "passive"))
    )
    (net (code "39") (name "Net-(IC4A-Q5)") (class "Default")
      (node (ref "IC4") (pin "6") (pinfunction "Q5_6") (pintype "output"))
      (node (ref "R10") (pin "2") (pinfunction "2_2") (pintype "passive"))
    )
    (net (code "40") (name "Net-(IC4A-Q6)") (class "Default")
      (node (ref "IC4") (pin "7") (pinfunction "Q6_7") (pintype "output"))
      (node (ref "R11") (pin "2") (pinfunction "2_2") (pintype "passive"))
    )
    (net (code "41") (name "Net-(IC4A-Q7)") (class "Default")
      (node (ref "IC4") (pin "4") (pinfunction "Q7_4") (pintype "output"))
      (node (ref "R8") (pin "2") (pinfunction "2_2") (pintype "passive"))
    )
    (net (code "42") (name "Net-(IC4A-Q8)") (class "Default")
      (node (ref "IC4") (pin "9") (pinfunction "Q8_9") (pintype "output"))
      (node (ref "R12") (pin "2") (pinfunction "2_2") (pintype "passive"))
    )
    (net (code "43") (name "Net-(IC4A-Q9)") (class "Default")
      (node (ref "IC4") (pin "5") (pinfunction "Q9_5") (pintype "output"))
      (node (ref "R9") (pin "2") (pinfunction "2_2") (pintype "passive"))
    )
    (net (code "44") (name "Net-(N1-A)") (class "Default")
      (node (ref "D5") (pin "C") (pinfunction "C_C") (pintype "passive"))
      (node (ref "N1") (pin "13") (pinfunction "A_13") (pintype "bidirectional"))
      (node (ref "R41") (pin "1") (pinfunction "1_1") (pintype "passive"))
    )
    (net (code "45") (name "Net-(N2-A)") (class "Default")
      (node (ref "D4") (pin "C") (pinfunction "C_C") (pintype "passive"))
      (node (ref "N2") (pin "13") (pinfunction "A_13") (pintype "bidirectional"))
      (node (ref "R4") (pin "1") (pinfunction "1_1") (pintype "passive"))
    )
    (net (code "46") (name "Net-(N3-A)") (class "Default")
      (node (ref "D6") (pin "C") (pinfunction "C_C") (pintype "passive"))
      (node (ref "N3") (pin "13") (pinfunction "A_13") (pintype "bidirectional"))
      (node (ref "R22") (pin "1") (pinfunction "1_1") (pintype "passive"))
    )
    (net (code "47") (name "Net-(N4-A)") (class "Default")
      (node (ref "D7") (pin "C") (pinfunction "C_C") (pintype "passive"))
      (node (ref "N4") (pin "13") (pinfunction "A_13") (pintype "bidirectional"))
      (node (ref "R26") (pin "1") (pinfunction "1_1") (pintype "passive"))
    )
    (net (code "48") (name "Net-(N5-A)") (class "Default")
      (node (ref "D8") (pin "C") (pinfunction "C_C") (pintype "passive"))
      (node (ref "N5") (pin "13") (pinfunction "A_13") (pintype "bidirectional"))
      (node (ref "R30") (pin "1") (pinfunction "1_1") (pintype "passive"))
    )
    (net (code "49") (name "Net-(N6-A)") (class "Default")
      (node (ref "D9") (pin "C") (pinfunction "C_C") (pintype "passive"))
      (node (ref "N6") (pin "13") (pinfunction "A_13") (pintype "bidirectional"))
      (node (ref "R34") (pin "1") (pinfunction "1_1") (pintype "passive"))
    )
    (net (code "50") (name "Net-(R1-Pad1)") (class "Default")
      (node (ref "R1") (pin "1") (pinfunction "1_1") (pintype "passive"))
      (node (ref "R2") (pin "2") (pinfunction "2_2") (pintype "passive"))
      (node (ref "T2") (pin "B") (pinfunction "B_B") (pintype "passive"))
    )
    (net (code "51") (name "Net-(R2-Pad1)") (class "Default")
      (node (ref "R2") (pin "1") (pinfunction "1_1") (pintype "passive"))
      (node (ref "T1") (pin "C") (pinfunction "C_C") (pintype "passive"))
    )
    (net (code "52") (name "Net-(R3-Pad1)") (class "Default")
      (node (ref "R3") (pin "1") (pinfunction "1_1") (pintype "passive"))
      (node (ref "T1") (pin "B") (pinfunction "B_B") (pintype "passive"))
    )
    (net (code "53") (name "Net-(R4-Pad2)") (class "Default")
      (node (ref "R4") (pin "2") (pinfunction "2_2") (pintype "passive"))
      (node (ref "T14") (pin "C") (pinfunction "C_C") (pintype "passive"))
    )
    (net (code "54") (name "Net-(R5-Pad1)") (class "Default")
      (node (ref "R5") (pin "1") (pinfunction "1_1") (pintype "passive"))
      (node (ref "T4") (pin "B") (pinfunction "B_B") (pintype "passive"))
    )
    (net (code "55") (name "Net-(R6-Pad1)") (class "Default")
      (node (ref "R6") (pin "1") (pinfunction "1_1") (pintype "passive"))
      (node (ref "T3") (pin "B") (pinfunction "B_B") (pintype "passive"))
    )
    (net (code "56") (name "Net-(R7-Pad1)") (class "Default")
      (node (ref "R7") (pin "1") (pinfunction "1_1") (pintype "passive"))
      (node (ref "T5") (pin "B") (pinfunction "B_B") (pintype "passive"))
    )
    (net (code "57") (name "Net-(R8-Pad1)") (class "Default")
      (node (ref "R8") (pin "1") (pinfunction "1_1") (pintype "passive"))
      (node (ref "T6") (pin "B") (pinfunction "B_B") (pintype "passive"))
    )
    (net (code "58") (name "Net-(R9-Pad1)") (class "Default")
      (node (ref "R9") (pin "1") (pinfunction "1_1") (pintype "passive"))
      (node (ref "T7") (pin "B") (pinfunction "B_B") (pintype "passive"))
    )
    (net (code "59") (name "Net-(R10-Pad1)") (class "Default")
      (node (ref "R10") (pin "1") (pinfunction "1_1") (pintype "passive"))
      (node (ref "T8") (pin "B") (pinfunction "B_B") (pintype "passive"))
    )
    (net (code "60") (name "Net-(R11-Pad1)") (class "Default")
      (node (ref "R11") (pin "1") (pinfunction "1_1") (pintype "passive"))
      (node (ref "T9") (pin "B") (pinfunction "B_B") (pintype "passive"))
    )
    (net (code "61") (name "Net-(R12-Pad1)") (class "Default")
      (node (ref "R12") (pin "1") (pinfunction "1_1") (pintype "passive"))
      (node (ref "T10") (pin "B") (pinfunction "B_B") (pintype "passive"))
    )
    (net (code "62") (name "Net-(R13-Pad1)") (class "Default")
      (node (ref "R13") (pin "1") (pinfunction "1_1") (pintype "passive"))
      (node (ref "T11") (pin "B") (pinfunction "B_B") (pintype "passive"))
    )
    (net (code "63") (name "Net-(R14-Pad1)") (class "Default")
      (node (ref "R14") (pin "1") (pinfunction "1_1") (pintype "passive"))
      (node (ref "T12") (pin "B") (pinfunction "B_B") (pintype "passive"))
    )
    (net (code "64") (name "Net-(R19-Pad1)") (class "Default")
      (node (ref "R19") (pin "1") (pinfunction "1_1") (pintype "passive"))
      (node (ref "R20") (pin "2") (pinfunction "2_2") (pintype "passive"))
      (node (ref "T14") (pin "B") (pinfunction "B_B") (pintype "passive"))
    )
    (net (code "65") (name "Net-(R20-Pad1)") (class "Default")
      (node (ref "R20") (pin "1") (pinfunction "1_1") (pintype "passive"))
      (node (ref "T13") (pin "C") (pinfunction "C_C") (pintype "passive"))
    )
    (net (code "66") (name "Net-(R21-Pad1)") (class "Default")
      (node (ref "R21") (pin "1") (pinfunction "1_1") (pintype "passive"))
      (node (ref "T13") (pin "B") (pinfunction "B_B") (pintype "passive"))
    )
    (net (code "67") (name "Net-(R22-Pad2)") (class "Default")
      (node (ref "R22") (pin "2") (pinfunction "2_2") (pintype "passive"))
      (node (ref "T16") (pin "C") (pinfunction "C_C") (pintype "passive"))
    )
    (net (code "68") (name "Net-(R23-Pad1)") (class "Default")
      (node (ref "R23") (pin "1") (pinfunction "1_1") (pintype "passive"))
      (node (ref "R24") (pin "2") (pinfunction "2_2") (pintype "passive"))
      (node (ref "T16") (pin "B") (pinfunction "B_B") (pintype "passive"))
    )
    (net (code "69") (name "Net-(R24-Pad1)") (class "Default")
      (node (ref "R24") (pin "1") (pinfunction "1_1") (pintype "passive"))
      (node (ref "T15") (pin "C") (pinfunction "C_C") (pintype "passive"))
    )
    (net (code "70") (name "Net-(R25-Pad1)") (class "Default")
      (node (ref "R25") (pin "1") (pinfunction "1_1") (pintype "passive"))
      (node (ref "T15") (pin "B") (pinfunction "B_B") (pintype "passive"))
    )
    (net (code "71") (name "Net-(R26-Pad2)") (class "Default")
      (node (ref "R26") (pin "2") (pinfunction "2_2") (pintype "passive"))
      (node (ref "T18") (pin "C") (pinfunction "C_C") (pintype "passive"))
    )
    (net (code "72") (name "Net-(R27-Pad1)") (class "Default")
      (node (ref "R27") (pin "1") (pinfunction "1_1") (pintype "passive"))
      (node (ref "R28") (pin "2") (pinfunction "2_2") (pintype "passive"))
      (node (ref "T18") (pin "B") (pinfunction "B_B") (pintype "passive"))
    )
    (net (code "73") (name "Net-(R28-Pad1)") (class "Default")
      (node (ref "R28") (pin "1") (pinfunction "1_1") (pintype "passive"))
      (node (ref "T17") (pin "C") (pinfunction "C_C") (pintype "passive"))
    )
    (net (code "74") (name "Net-(R29-Pad1)") (class "Default")
      (node (ref "R29") (pin "1") (pinfunction "1_1") (pintype "passive"))
      (node (ref "T17") (pin "B") (pinfunction "B_B") (pintype "passive"))
    )
    (net (code "75") (name "Net-(R30-Pad2)") (class "Default")
      (node (ref "R30") (pin "2") (pinfunction "2_2") (pintype "passive"))
      (node (ref "T20") (pin "C") (pinfunction "C_C") (pintype "passive"))
    )
    (net (code "76") (name "Net-(R31-Pad1)") (class "Default")
      (node (ref "R31") (pin "1") (pinfunction "1_1") (pintype "passive"))
      (node (ref "R32") (pin "2") (pinfunction "2_2") (pintype "passive"))
      (node (ref "T20") (pin "B") (pinfunction "B_B") (pintype "passive"))
    )
    (net (code "77") (name "Net-(R32-Pad1)") (class "Default")
      (node (ref "R32") (pin "1") (pinfunction "1_1") (pintype "passive"))
      (node (ref "T19") (pin "C") (pinfunction "C_C") (pintype "passive"))
    )
    (net (code "78") (name "Net-(R33-Pad1)") (class "Default")
      (node (ref "R33") (pin "1") (pinfunction "1_1") (pintype "passive"))
      (node (ref "T19") (pin "B") (pinfunction "B_B") (pintype "passive"))
    )
    (net (code "79") (name "Net-(R34-Pad2)") (class "Default")
      (node (ref "R34") (pin "2") (pinfunction "2_2") (pintype "passive"))
      (node (ref "T22") (pin "C") (pinfunction "C_C") (pintype "passive"))
    )
    (net (code "80") (name "Net-(R35-Pad1)") (class "Default")
      (node (ref "R35") (pin "1") (pinfunction "1_1") (pintype "passive"))
      (node (ref "R36") (pin "2") (pinfunction "2_2") (pintype "passive"))
      (node (ref "T22") (pin "B") (pinfunction "B_B") (pintype "passive"))
    )
    (net (code "81") (name "Net-(R36-Pad1)") (class "Default")
      (node (ref "R36") (pin "1") (pinfunction "1_1") (pintype "passive"))
      (node (ref "T21") (pin "C") (pinfunction "C_C") (pintype "passive"))
    )
    (net (code "82") (name "Net-(R37-Pad1)") (class "Default")
      (node (ref "R37") (pin "1") (pinfunction "1_1") (pintype "passive"))
      (node (ref "T21") (pin "B") (pinfunction "B_B") (pintype "passive"))
    )
    (net (code "83") (name "Net-(R41-Pad2)") (class "Default")
      (node (ref "R41") (pin "2") (pinfunction "2_2") (pintype "passive"))
      (node (ref "T2") (pin "C") (pinfunction "C_C") (pintype "passive"))
    )
    (net (code "84") (name "Net-(S1-P)") (class "Default")
      (node (ref "JP1") (pin "2") (pinfunction "2_2") (pintype "passive"))
      (node (ref "S1") (pin "3") (pinfunction "P_3") (pintype "passive"))
      (node (ref "S1") (pin "4") (pinfunction "P1_4") (pintype "passive"))
      (node (ref "U1") (pin "3") (pinfunction "PIO0_12_3") (pintype "bidirectional"))
    )
    (net (code "85") (name "Net-(S2-P)") (class "Default")
      (node (ref "S2") (pin "3") (pinfunction "P_3") (pintype "passive"))
      (node (ref "S2") (pin "4") (pinfunction "P1_4") (pintype "passive"))
      (node (ref "SV1") (pin "15") (pinfunction "15_15") (pintype "passive"))
      (node (ref "U1") (pin "4") (pinfunction "~{RESET}/PIO0_5_4") (pintype "bidirectional"))
    )
    (net (code "86") (name "Net-(U1-PIO0_0{slash}ACMP_I1{slash}TDO)") (class "Default")
      (node (ref "U$1") (pin "TX") (pinfunction "TX_TX") (pintype "bidirectional"))
      (node (ref "U1") (pin "19") (pinfunction "PIO0_0/ACMP_I1/TDO_19") (pintype "bidirectional"))
    )
    (net (code "87") (name "Net-(U1-PIO0_6{slash}VDDCMP)") (class "Default")
      (node (ref "U$1") (pin "RX") (pinfunction "RX_RX") (pintype "bidirectional"))
      (node (ref "U1") (pin "18") (pinfunction "PIO0_6/VDDCMP_18") (pintype "bidirectional"))
    )
    (net (code "88") (name "Net-(U1-PIO0_8{slash}XTALIN)") (class "Default")
      (node (ref "C9") (pin "1") (pinfunction "1_1") (pintype "passive"))
      (node (ref "U1") (pin "14") (pinfunction "PIO0_8/XTALIN_14") (pintype "bidirectional"))
      (node (ref "X1") (pin "3") (pinfunction "PIN2_3") (pintype "bidirectional"))
    )
    (net (code "89") (name "Net-(U1-PIO0_9{slash}XTALOUT)") (class "Default")
      (node (ref "C8") (pin "1") (pinfunction "1_1") (pintype "passive"))
      (node (ref "U1") (pin "13") (pinfunction "PIO0_9/XTALOUT_13") (pintype "bidirectional"))
      (node (ref "X1") (pin "1") (pinfunction "PIN1_1") (pintype "bidirectional"))
    )
    (net (code "90") (name "Net-(U1-SWCLK{slash}PIO0_3{slash}TCK)") (class "Default")
      (node (ref "SV1") (pin "9") (pinfunction "9_9") (pintype "passive"))
      (node (ref "U1") (pin "6") (pinfunction "SWCLK/PIO0_3/TCK_6") (pintype "bidirectional"))
    )
    (net (code "91") (name "Net-(U1-SWDIO{slash}PIO0_2{slash}TMS)") (class "Default")
      (node (ref "SV1") (pin "7") (pinfunction "7_7") (pintype "passive"))
      (node (ref "U1") (pin "7") (pinfunction "SWDIO/PIO0_2/TMS_7") (pintype "bidirectional"))
    )
    (net (code "92") (name "S1") (class "Default")
      (node (ref "R33") (pin "2") (pinfunction "2_2") (pintype "passive"))
      (node (ref "U1") (pin "17") (pinfunction "PIO0_7_17") (pintype "bidirectional"))
    )
    (net (code "93") (name "S2") (class "Default")
      (node (ref "R37") (pin "2") (pinfunction "2_2") (pintype "passive"))
      (node (ref "U1") (pin "20") (pinfunction "PIO0_14_20") (pintype "bidirectional"))
    )
    (net (code "94") (name "unconnected-(SV1-Pad2)") (class "Default")
      (node (ref "SV1") (pin "2") (pinfunction "2_2") (pintype "passive"))
    )
    (net (code "95") (name "unconnected-(SV1-Pad3)") (class "Default")
      (node (ref "SV1") (pin "3") (pinfunction "3_3") (pintype "passive"))
    )
    (net (code "96") (name "unconnected-(SV1-Pad5)") (class "Default")
      (node (ref "SV1") (pin "5") (pinfunction "5_5") (pintype "passive"))
    )
    (net (code "97") (name "unconnected-(SV1-Pad11)") (class "Default")
      (node (ref "SV1") (pin "11") (pinfunction "11_11") (pintype "passive"))
    )
    (net (code "98") (name "unconnected-(SV1-Pad13)") (class "Default")
      (node (ref "SV1") (pin "13") (pinfunction "13_13") (pintype "passive"))
    )
    (net (code "99") (name "unconnected-(SV1-Pad17)") (class "Default")
      (node (ref "SV1") (pin "17") (pinfunction "17_17") (pintype "passive"))
    )
    (net (code "100") (name "unconnected-(SV1-Pad19)") (class "Default")
      (node (ref "SV1") (pin "19") (pinfunction "19_19") (pintype "passive"))
    )
    (net (code "101") (name "unconnected-(U$1-PadRST)") (class "Default")
      (node (ref "U$1") (pin "RST") (pinfunction "RST_RST") (pintype "bidirectional"))
    )
  )
)
